# SJ2088POE_USB.net
KiCad netlist of a schematic drawn in Altium Designer
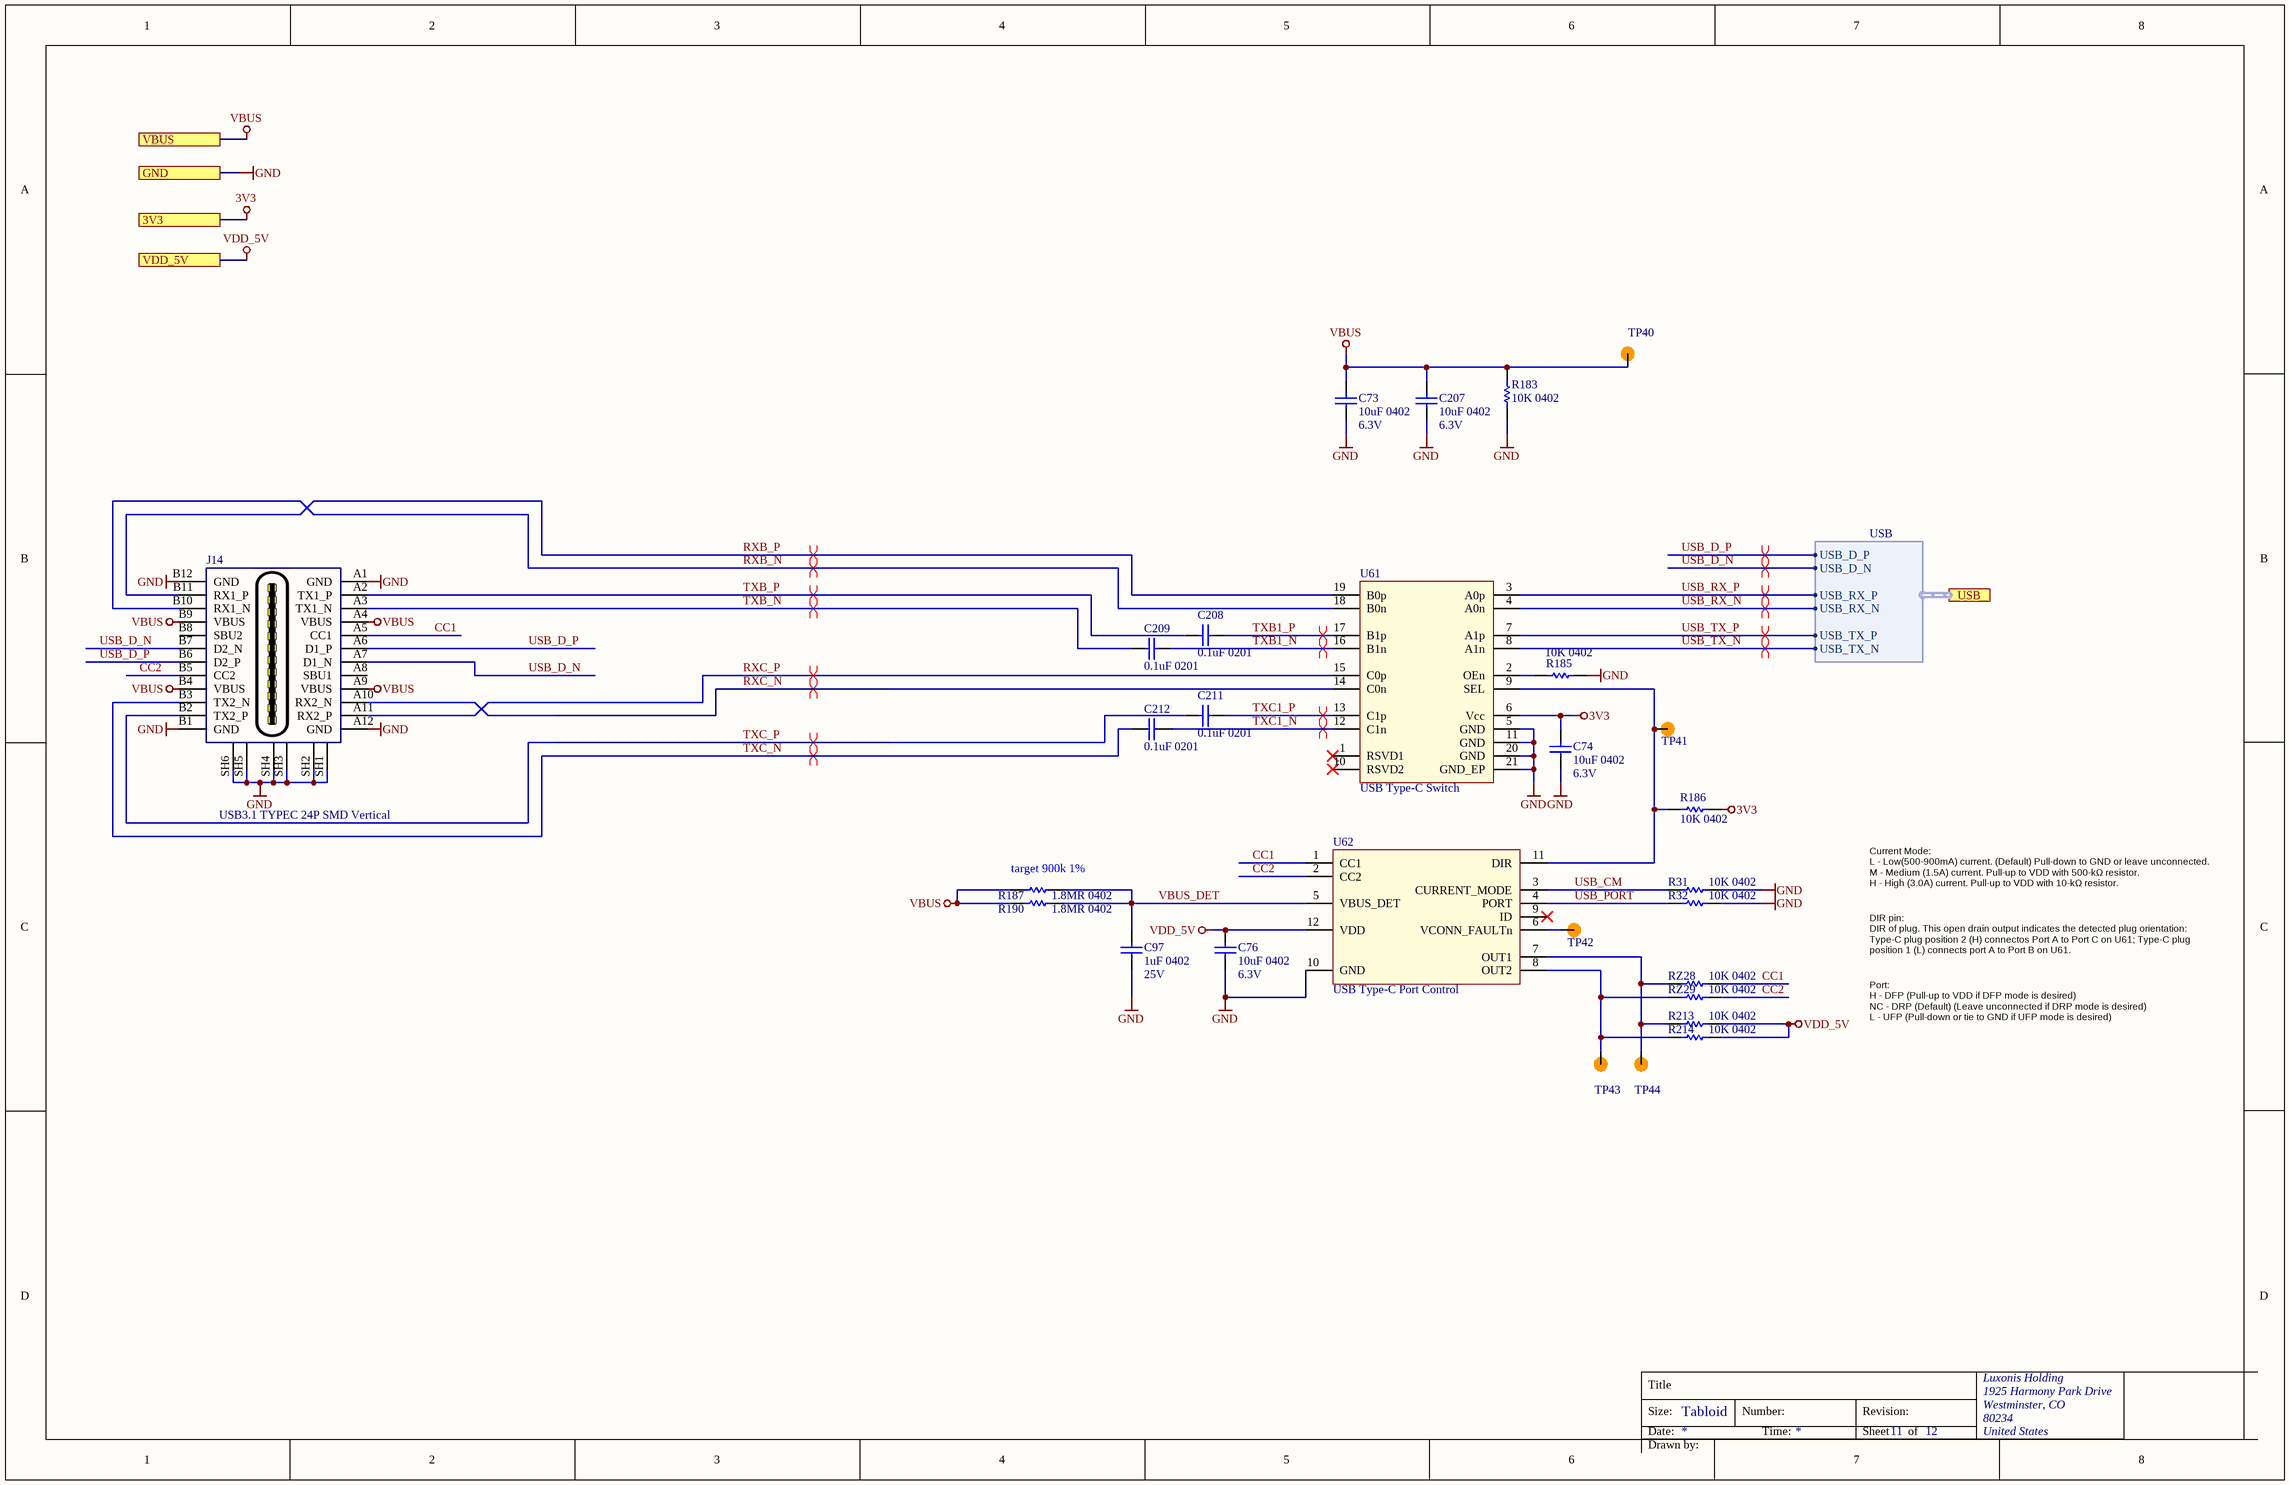
[diagram p0: SJ2088POE_USB.SchDoc]

(export (version "E")
  (design (tool "Eeschema 10.0.6"))
  (components
    (comp (ref "C73")
      (value "10uF 0402")
      (footprint "CAP_Altium_Vault_Generic:CAPC0402(1005)70_N")
      (description "CAP CER 10UF 6.3V X5R 0402 20%")
      (fields (field (name "TOLERANCE") "20%") (field (name "VOLTAGE RATING") "6.3V"))
      (libsource (lib "LuxonisMaster") (part "GRM155R60J106ME15D"))
    )
    (comp (ref "C74")
      (value "10uF 0402")
      (footprint "CAP_Altium_Vault_Generic:CAPC0402(1005)70_N")
      (description "CAP CER 10UF 6.3V X5R 0402 20%")
      (fields (field (name "TOLERANCE") "20%") (field (name "VOLTAGE RATING") "6.3V"))
      (libsource (lib "LuxonisMaster") (part "GRM155R60J106ME15D"))
    )
    (comp (ref "C76")
      (value "10uF 0402")
      (footprint "CAP_Altium_Vault_Generic:CAPC0402(1005)70_N")
      (description "CAP CER 10UF 6.3V X5R 0402 20%")
      (fields (field (name "TOLERANCE") "20%") (field (name "VOLTAGE RATING") "6.3V"))
      (libsource (lib "LuxonisMaster") (part "GRM155R60J106ME15D"))
    )
    (comp (ref "C97")
      (value "1uF 0402")
      (footprint "CAP_Altium_Vault_Generic:CAPC0402(1005)70_N")
      (description "CAP CER 1UF 25V X5R 0402 10%")
      (fields
        (field (name "TOLERANCE") "10%")
        (field (name "VOLTAGE") "25V")
        (field (name "VOLTAGE RATING") "25V")
      )
      (libsource (lib "LuxonisMaster") (part "GRM155R61E105KA12D"))
    )
    (comp (ref "C207")
      (value "10uF 0402")
      (footprint "CAP_Altium_Vault_Generic:CAPC0402(1005)70_N")
      (description "CAP CER 10UF 6.3V X5R 0402 20%")
      (fields (field (name "TOLERANCE") "20%") (field (name "VOLTAGE RATING") "6.3V"))
      (libsource (lib "LuxonisMaster") (part "GRM155R60J106ME15D"))
    )
    (comp (ref "C208")
      (value "0.1uF 0201")
      (footprint "CAP_Altium_Vault_Generic:CAPC0201(0603)33_L")
      (description "CAP CER 0.1UF 10V X5R 0201")
      (fields (field (name "TOLERANCE") "10%") (field (name "VOLTAGE") "10V"))
      (libsource (lib "LuxonisMaster") (part "GRM033R61A104KE15D"))
    )
    (comp (ref "C209")
      (value "0.1uF 0201")
      (footprint "CAP_Altium_Vault_Generic:CAPC0201(0603)33_L")
      (description "CAP CER 0.1UF 10V X5R 0201")
      (fields (field (name "TOLERANCE") "10%") (field (name "VOLTAGE") "10V"))
      (libsource (lib "LuxonisMaster") (part "GRM033R61A104KE15D"))
    )
    (comp (ref "C211")
      (value "0.1uF 0201")
      (footprint "CAP_Altium_Vault_Generic:CAPC0201(0603)33_L")
      (description "CAP CER 0.1UF 10V X5R 0201")
      (fields (field (name "TOLERANCE") "10%") (field (name "VOLTAGE") "10V"))
      (libsource (lib "LuxonisMaster") (part "GRM033R61A104KE15D"))
    )
    (comp (ref "C212")
      (value "0.1uF 0201")
      (footprint "CAP_Altium_Vault_Generic:CAPC0201(0603)33_L")
      (description "CAP CER 0.1UF 10V X5R 0201")
      (fields (field (name "TOLERANCE") "10%") (field (name "VOLTAGE") "10V"))
      (libsource (lib "LuxonisMaster") (part "GRM033R61A104KE15D"))
    )
    (comp (ref "J14")
      (value "USB3.1 TYPEC 24P SMD Vertical")
      (footprint "SJ2088POE:CX80B1-24P")
      (description "CONN RCPT USB3.1 TYPEC 24POS SMD Vertical")
      (libsource (lib "SJ2088POE") (part "CX80B1-24P"))
    )
    (comp (ref "R31")
      (value "10K 0402")
      (footprint "RES_Altium_Vault_Generic:RESC0402(1005)_N")
      (fields (field (name "TOLERANCE") "1%"))
      (libsource (lib "LuxonisMaster") (part "RC0402FR-1310KL"))
    )
    (comp (ref "R32")
      (value "10K 0402")
      (footprint "RES_Altium_Vault_Generic:RESC0402(1005)_N")
      (fields (field (name "TOLERANCE") "1%"))
      (libsource (lib "LuxonisMaster") (part "RC0402FR-1310KL"))
    )
    (comp (ref "R183")
      (value "10K 0402")
      (footprint "RES_Altium_Vault_Generic:RESC0402(1005)_N")
      (fields (field (name "TOLERANCE") "1%"))
      (libsource (lib "LuxonisMaster") (part "RC0402FR-1310KL"))
    )
    (comp (ref "R185")
      (value "10K 0402")
      (footprint "RES_Altium_Vault_Generic:RESC0402(1005)_N")
      (fields (field (name "TOLERANCE") "1%"))
      (libsource (lib "LuxonisMaster") (part "RC0402FR-1310KL"))
    )
    (comp (ref "R186")
      (value "10K 0402")
      (footprint "RES_Altium_Vault_Generic:RESC0402(1005)_N")
      (fields (field (name "TOLERANCE") "1%"))
      (libsource (lib "LuxonisMaster") (part "RC0402FR-1310KL"))
    )
    (comp (ref "R187")
      (value "1.8MR 0402")
      (footprint "RES_Altium_Vault_Generic:RESC0402(1005)_N")
      (description "RES SMD 1.8M OHM 1% 1/16W 0402")
      (fields (field (name "TOLERANCE") "1%"))
      (libsource (lib "LuxonisMaster") (part "CRCW04021M80FKED"))
    )
    (comp (ref "R190")
      (value "1.8MR 0402")
      (footprint "RES_Altium_Vault_Generic:RESC0402(1005)_N")
      (description "RES SMD 1.8M OHM 1% 1/16W 0402")
      (fields (field (name "TOLERANCE") "1%"))
      (libsource (lib "LuxonisMaster") (part "CRCW04021M80FKED"))
    )
    (comp (ref "R213")
      (value "10K 0402")
      (footprint "RES_Altium_Vault_Generic:RESC0402(1005)_N")
      (fields (field (name "TOLERANCE") "1%"))
      (libsource (lib "LuxonisMaster") (part "RC0402FR-1310KL"))
    )
    (comp (ref "R214")
      (value "10K 0402")
      (footprint "RES_Altium_Vault_Generic:RESC0402(1005)_N")
      (fields (field (name "TOLERANCE") "1%"))
      (libsource (lib "LuxonisMaster") (part "RC0402FR-1310KL"))
    )
    (comp (ref "RZ28")
      (value "10K 0402")
      (footprint "RES_Altium_Vault_Generic:RESC0402(1005)_N")
      (fields (field (name "TOLERANCE") "1%"))
      (libsource (lib "LuxonisMaster") (part "RC0402FR-1310KL"))
    )
    (comp (ref "RZ29")
      (value "10K 0402")
      (footprint "RES_Altium_Vault_Generic:RESC0402(1005)_N")
      (fields (field (name "TOLERANCE") "1%"))
      (libsource (lib "LuxonisMaster") (part "RC0402FR-1310KL"))
    )
    (comp (ref "TP40")
      (value "TP100_200_NS")
      (footprint "LuxonisMaster:TP100_200_NS")
      (libsource (lib "LuxonisMaster") (part "TEST_POINT"))
    )
    (comp (ref "TP41")
      (value "TP100_200_NS")
      (footprint "LuxonisMaster:TP100_200_NS")
      (libsource (lib "LuxonisMaster") (part "TEST_POINT"))
    )
    (comp (ref "TP42")
      (value "TP100_200_NS")
      (footprint "LuxonisMaster:TP100_200_NS")
      (libsource (lib "LuxonisMaster") (part "TEST_POINT"))
    )
    (comp (ref "TP43")
      (value "TP100_200_NS")
      (footprint "LuxonisMaster:TP100_200_NS")
      (libsource (lib "LuxonisMaster") (part "TEST_POINT"))
    )
    (comp (ref "TP44")
      (value "TP100_200_NS")
      (footprint "LuxonisMaster:TP100_200_NS")
      (libsource (lib "LuxonisMaster") (part "TEST_POINT"))
    )
    (comp (ref "U61")
      (value "USB Type-C Switch")
      (footprint "LuxonisMaster:HD3SS3212RKSR")
      (description "IC MUX 2:1 8 OHM 20VQFN")
      (libsource (lib "LuxonisMaster") (part "HD3SS3212RKSR"))
    )
    (comp (ref "U62")
      (value "USB Type-C Port Control")
      (footprint "LuxonisMaster:TUSB321RWBR")
      (description "IC USB PORT CONTROL TYPE-C 12X2Q")
      (libsource (lib "LuxonisMaster") (part "TUSB321RWBR"))
    )
  )
  (nets
    (net (code "2") (name "/CC1") (class "Default")
      (node (ref "J14") (pin "A5") (pinfunction "CC1_A5") (pintype "passive"))
      (node (ref "RZ28") (pin "2") (pinfunction "2_2") (pintype "passive"))
      (node (ref "U62") (pin "1") (pinfunction "CC1_1") (pintype "passive"))
    )
    (net (code "3") (name "/CC2") (class "Default")
      (node (ref "J14") (pin "B5") (pinfunction "CC2_B5") (pintype "passive"))
      (node (ref "RZ29") (pin "2") (pinfunction "2_2") (pintype "passive"))
      (node (ref "U62") (pin "2") (pinfunction "CC2_2") (pintype "passive"))
    )
    (net (code "4") (name "/RXB_N") (class "Default")
      (node (ref "J14") (pin "B10") (pinfunction "RX1_N_B10") (pintype "passive"))
      (node (ref "U61") (pin "18") (pinfunction "B0n_18") (pintype "passive"))
    )
    (net (code "5") (name "/RXB_P") (class "Default")
      (node (ref "J14") (pin "B11") (pinfunction "RX1_P_B11") (pintype "passive"))
      (node (ref "U61") (pin "19") (pinfunction "B0p_19") (pintype "passive"))
    )
    (net (code "6") (name "/RXC_N") (class "Default")
      (node (ref "J14") (pin "A10") (pinfunction "RX2_N_A10") (pintype "passive"))
      (node (ref "U61") (pin "14") (pinfunction "C0n_14") (pintype "passive"))
    )
    (net (code "7") (name "/RXC_P") (class "Default")
      (node (ref "J14") (pin "A11") (pinfunction "RX2_P_A11") (pintype "passive"))
      (node (ref "U61") (pin "15") (pinfunction "C0p_15") (pintype "passive"))
    )
    (net (code "8") (name "/TXB1_N") (class "Default")
      (node (ref "C209") (pin "2") (pinfunction "2_2") (pintype "passive"))
      (node (ref "U61") (pin "16") (pinfunction "B1n_16") (pintype "passive"))
    )
    (net (code "9") (name "/TXB1_P") (class "Default")
      (node (ref "C208") (pin "2") (pinfunction "2_2") (pintype "passive"))
      (node (ref "U61") (pin "17") (pinfunction "B1p_17") (pintype "passive"))
    )
    (net (code "10") (name "/TXB_N") (class "Default")
      (node (ref "C209") (pin "1") (pinfunction "1_1") (pintype "passive"))
      (node (ref "J14") (pin "A3") (pinfunction "TX1_N_A3") (pintype "passive"))
    )
    (net (code "11") (name "/TXB_P") (class "Default")
      (node (ref "C208") (pin "1") (pinfunction "1_1") (pintype "passive"))
      (node (ref "J14") (pin "A2") (pinfunction "TX1_P_A2") (pintype "passive"))
    )
    (net (code "12") (name "/TXC1_N") (class "Default")
      (node (ref "C212") (pin "2") (pinfunction "2_2") (pintype "passive"))
      (node (ref "U61") (pin "12") (pinfunction "C1n_12") (pintype "passive"))
    )
    (net (code "13") (name "/TXC1_P") (class "Default")
      (node (ref "C211") (pin "2") (pinfunction "2_2") (pintype "passive"))
      (node (ref "U61") (pin "13") (pinfunction "C1p_13") (pintype "passive"))
    )
    (net (code "14") (name "/TXC_N") (class "Default")
      (node (ref "C212") (pin "1") (pinfunction "1_1") (pintype "passive"))
      (node (ref "J14") (pin "B3") (pinfunction "TX2_N_B3") (pintype "passive"))
    )
    (net (code "15") (name "/TXC_P") (class "Default")
      (node (ref "C211") (pin "1") (pinfunction "1_1") (pintype "passive"))
      (node (ref "J14") (pin "B2") (pinfunction "TX2_P_B2") (pintype "passive"))
    )
    (net (code "16") (name "/USB_CM") (class "Default")
      (node (ref "R31") (pin "1") (pinfunction "1_1") (pintype "passive"))
      (node (ref "U62") (pin "3") (pinfunction "CURRENT_MODE_3") (pintype "passive"))
    )
    (net (code "17") (name "/USB_D_N") (class "Default")
      (node (ref "J14") (pin "A7") (pinfunction "D1_N_A7") (pintype "passive"))
      (node (ref "J14") (pin "B7") (pinfunction "D2_N_B7") (pintype "passive"))
    )
    (net (code "18") (name "/USB_D_P") (class "Default")
      (node (ref "J14") (pin "A6") (pinfunction "D1_P_A6") (pintype "passive"))
      (node (ref "J14") (pin "B6") (pinfunction "D2_P_B6") (pintype "passive"))
    )
    (net (code "19") (name "/USB_PORT") (class "Default")
      (node (ref "R32") (pin "1") (pinfunction "1_1") (pintype "passive"))
      (node (ref "U62") (pin "4") (pinfunction "PORT_4") (pintype "passive"))
    )
    (net (code "20") (name "/USB_RX_N") (class "Default")
      (node (ref "U61") (pin "4") (pinfunction "A0n_4") (pintype "passive"))
    )
    (net (code "21") (name "/USB_RX_P") (class "Default")
      (node (ref "U61") (pin "3") (pinfunction "A0p_3") (pintype "passive"))
    )
    (net (code "22") (name "/USB_TX_N") (class "Default")
      (node (ref "U61") (pin "8") (pinfunction "A1n_8") (pintype "passive"))
    )
    (net (code "23") (name "/USB_TX_P") (class "Default")
      (node (ref "U61") (pin "7") (pinfunction "A1p_7") (pintype "passive"))
    )
    (net (code "24") (name "/VBUS_DET") (class "Default")
      (node (ref "C97") (pin "2") (pinfunction "2_2") (pintype "passive"))
      (node (ref "R187") (pin "2") (pinfunction "2_2") (pintype "passive"))
      (node (ref "R190") (pin "2") (pinfunction "2_2") (pintype "passive"))
      (node (ref "U62") (pin "5") (pinfunction "VBUS_DET_5") (pintype "passive"))
    )
    (net (code "26") (name "3V3") (class "Default")
      (node (ref "C74") (pin "2") (pinfunction "2_2") (pintype "passive"))
      (node (ref "R186") (pin "2") (pinfunction "2_2") (pintype "passive"))
      (node (ref "U61") (pin "6") (pinfunction "Vcc_6") (pintype "passive"))
    )
    (net (code "27") (name "GND") (class "Default")
      (node (ref "C207") (pin "1") (pinfunction "1_1") (pintype "passive"))
      (node (ref "C73") (pin "1") (pinfunction "1_1") (pintype "passive"))
      (node (ref "C74") (pin "1") (pinfunction "1_1") (pintype "passive"))
      (node (ref "C76") (pin "1") (pinfunction "1_1") (pintype "passive"))
      (node (ref "C97") (pin "1") (pinfunction "1_1") (pintype "passive"))
      (node (ref "J14") (pin "A1") (pinfunction "GND_A1") (pintype "passive"))
      (node (ref "J14") (pin "A12") (pinfunction "GND_A12") (pintype "passive"))
      (node (ref "J14") (pin "B1") (pinfunction "GND_B1") (pintype "passive"))
      (node (ref "J14") (pin "B12") (pinfunction "GND_B12") (pintype "passive"))
      (node (ref "J14") (pin "SH1") (pinfunction "SH_SH1") (pintype "passive"))
      (node (ref "J14") (pin "SH2") (pinfunction "SH_SH2") (pintype "passive"))
      (node (ref "J14") (pin "SH3") (pinfunction "SH_SH3") (pintype "passive"))
      (node (ref "J14") (pin "SH4") (pinfunction "SH_SH4") (pintype "passive"))
      (node (ref "J14") (pin "SH5") (pinfunction "SH_SH5") (pintype "passive"))
      (node (ref "J14") (pin "SH6") (pinfunction "SH_SH6") (pintype "passive"))
      (node (ref "R183") (pin "1") (pinfunction "1_1") (pintype "passive"))
      (node (ref "R185") (pin "2") (pinfunction "2_2") (pintype "passive"))
      (node (ref "R31") (pin "2") (pinfunction "2_2") (pintype "passive"))
      (node (ref "R32") (pin "2") (pinfunction "2_2") (pintype "passive"))
      (node (ref "U61") (pin "11") (pinfunction "GND_11") (pintype "passive"))
      (node (ref "U61") (pin "20") (pinfunction "GND_20") (pintype "passive"))
      (node (ref "U61") (pin "21") (pinfunction "GND_EP_21") (pintype "passive"))
      (node (ref "U61") (pin "5") (pinfunction "GND_5") (pintype "passive"))
      (node (ref "U62") (pin "10") (pinfunction "GND_10") (pintype "passive"))
    )
    (net (code "28") (name "Net-(U61-OEn)") (class "Default")
      (node (ref "R185") (pin "1") (pinfunction "1_1") (pintype "passive"))
      (node (ref "U61") (pin "2") (pinfunction "OEn_2") (pintype "passive"))
    )
    (net (code "29") (name "Net-(U61-SEL)") (class "Default")
      (node (ref "R186") (pin "1") (pinfunction "1_1") (pintype "passive"))
      (node (ref "TP41") (pin "1") (pintype "passive"))
      (node (ref "U61") (pin "9") (pinfunction "SEL_9") (pintype "passive"))
      (node (ref "U62") (pin "11") (pinfunction "DIR_11") (pintype "passive"))
    )
    (net (code "30") (name "Net-(U62-OUT1)") (class "Default")
      (node (ref "R213") (pin "1") (pinfunction "1_1") (pintype "passive"))
      (node (ref "RZ28") (pin "1") (pinfunction "1_1") (pintype "passive"))
      (node (ref "TP44") (pin "1") (pintype "passive"))
      (node (ref "U62") (pin "7") (pinfunction "OUT1_7") (pintype "passive"))
    )
    (net (code "31") (name "Net-(U62-OUT2)") (class "Default")
      (node (ref "R214") (pin "1") (pinfunction "1_1") (pintype "passive"))
      (node (ref "RZ29") (pin "1") (pinfunction "1_1") (pintype "passive"))
      (node (ref "TP43") (pin "1") (pintype "passive"))
      (node (ref "U62") (pin "8") (pinfunction "OUT2_8") (pintype "passive"))
    )
    (net (code "32") (name "Net-(U62-VCONN_FAULTn)") (class "Default")
      (node (ref "TP42") (pin "1") (pintype "passive"))
      (node (ref "U62") (pin "6") (pinfunction "VCONN_FAULTn_6") (pintype "passive"))
    )
    (net (code "33") (name "VBUS") (class "Default")
      (node (ref "C207") (pin "2") (pinfunction "2_2") (pintype "passive"))
      (node (ref "C73") (pin "2") (pinfunction "2_2") (pintype "passive"))
      (node (ref "J14") (pin "A4") (pinfunction "VBUS_A4") (pintype "passive"))
      (node (ref "J14") (pin "A9") (pinfunction "VBUS_A9") (pintype "passive"))
      (node (ref "J14") (pin "B4") (pinfunction "VBUS_B4") (pintype "passive"))
      (node (ref "J14") (pin "B9") (pinfunction "VBUS_B9") (pintype "passive"))
      (node (ref "R183") (pin "2") (pinfunction "2_2") (pintype "passive"))
      (node (ref "R187") (pin "1") (pinfunction "1_1") (pintype "passive"))
      (node (ref "R190") (pin "1") (pinfunction "1_1") (pintype "passive"))
      (node (ref "TP40") (pin "1") (pintype "passive"))
    )
    (net (code "34") (name "VDD_5V") (class "Default")
      (node (ref "C76") (pin "2") (pinfunction "2_2") (pintype "passive"))
      (node (ref "R213") (pin "2") (pinfunction "2_2") (pintype "passive"))
      (node (ref "R214") (pin "2") (pinfunction "2_2") (pintype "passive"))
      (node (ref "U62") (pin "12") (pinfunction "VDD_12") (pintype "passive"))
    )
    (net (code "35") (name "unconnected-(J14-SBU1-PadA8)") (class "Default")
      (node (ref "J14") (pin "A8") (pinfunction "SBU1_A8") (pintype "passive"))
    )
    (net (code "36") (name "unconnected-(J14-SBU2-PadB8)") (class "Default")
      (node (ref "J14") (pin "B8") (pinfunction "SBU2_B8") (pintype "passive"))
    )
    (net (code "37") (name "unconnected-(U61-RSVD1-Pad1)") (class "Default")
      (node (ref "U61") (pin "1") (pinfunction "RSVD1_1") (pintype "passive+no_connect"))
    )
    (net (code "38") (name "unconnected-(U61-RSVD2-Pad10)") (class "Default")
      (node (ref "U61") (pin "10") (pinfunction "RSVD2_10") (pintype "passive+no_connect"))
    )
    (net (code "39") (name "unconnected-(U62-ID-Pad9)") (class "Default")
      (node (ref "U62") (pin "9") (pinfunction "ID_9") (pintype "passive+no_connect"))
    )
  )
)
